# S7CAS-PLEIADES-CARTE-MERE_P07_LOW_POWER.net
KiCad netlist of a schematic drawn in Altium Designer
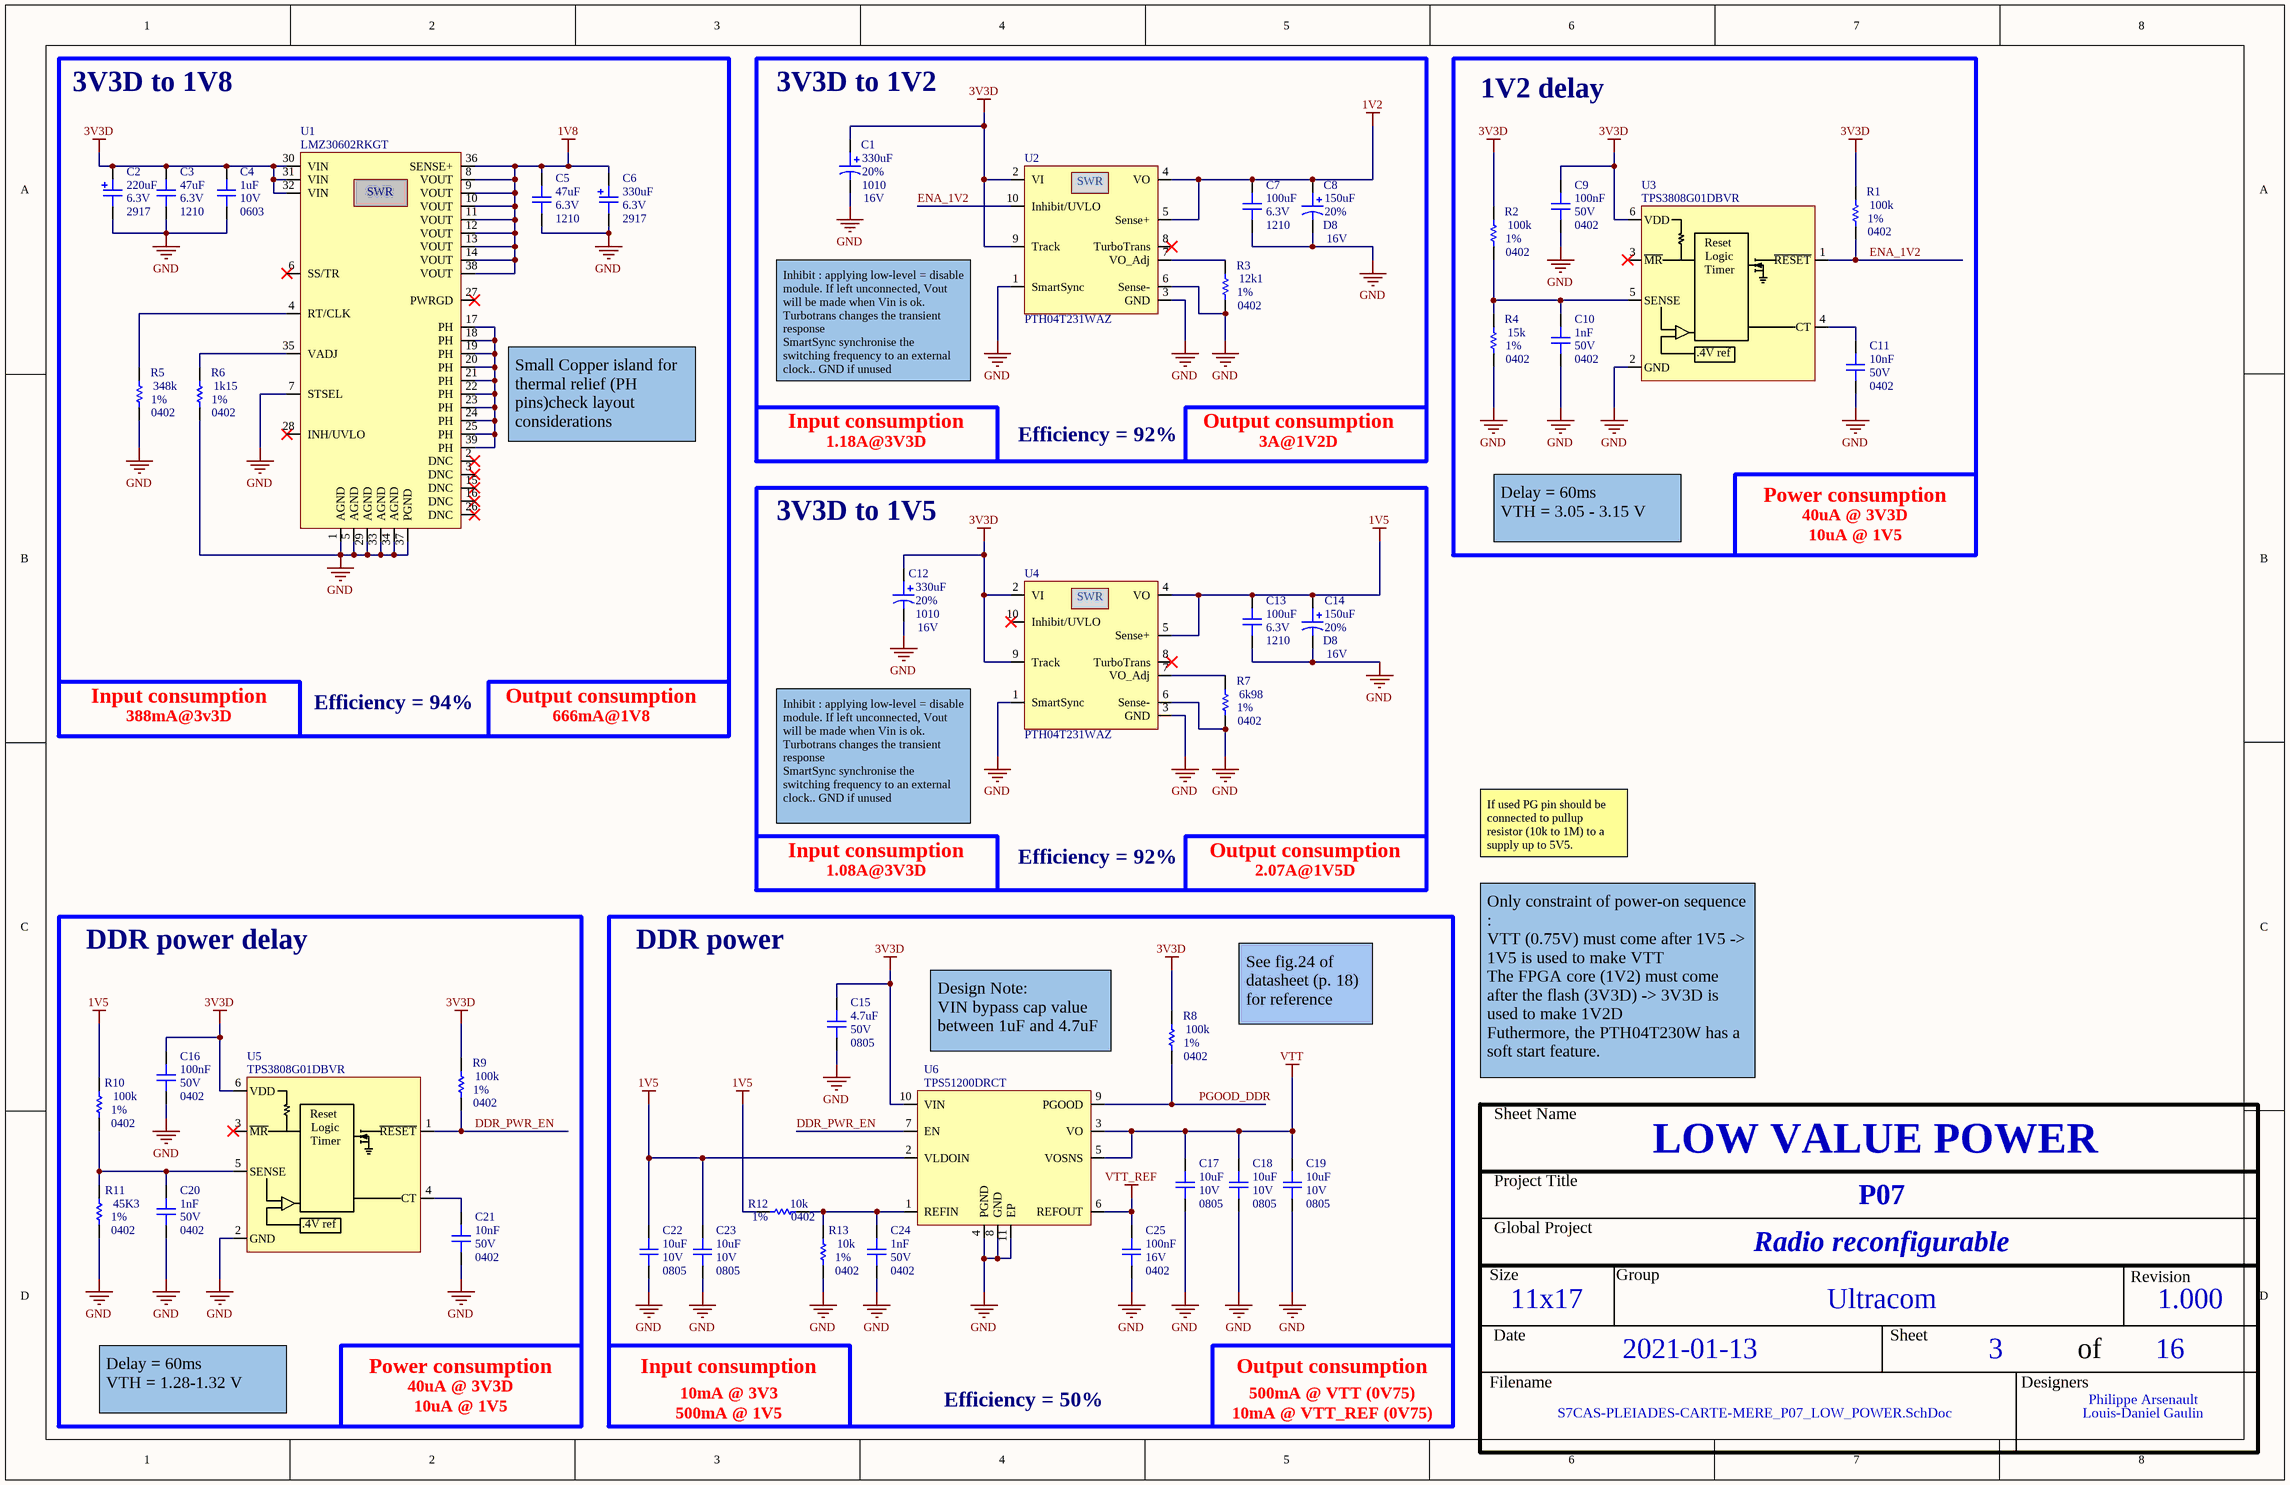
[diagram p0: S7CAS-PLEIADES-CARTE-MERE_P07_LOW_POWER.SchDoc]

(export (version "E")
  (design (tool "Eeschema 10.0.6"))
  (components
    (comp (ref "C1")
      (value "330uF")
      (footprint "CAP_ALU_1010_vishay")
      (description "CAP - ALU 330uF 20% 16V - 1010")
      (fields
        (field (name "MFG") "Vishay Dale")
        (field (name "MFG PART NUMBER") "MAL214699501E3")
        (field (name "VOLTAGE") "16V")
        (field (name "PACKAGE") "1010")
        (field (name "PRECISION") "20%")
        (field (name "CREATEDBY") "Jonathan Bouchard")
      )
      (libsource (lib "S7CAS_LIB2021") (part "CAP_ALU_MAL214699501E3"))
    )
    (comp (ref "C2")
      (value "220uF")
      (footprint "CAP_TAN_2917(D)")
      (description "CAP - TANTALUM - 2917")
      (fields
        (field (name "VOLTAGE") "6.3V")
        (field (name "PACKAGE") "2917")
        (field (name "Comment") "CAP - TANTALUM - CASE D")
        (field (name "CREATEDBY") "Jonathan Bouchard")
      )
      (libsource (lib "S7CAS_LIB2021") (part "CAP_TANT_2917(D)"))
    )
    (comp (ref "C3")
      (value "47uF")
      (footprint "CAP_1210")
      (description "CAP - 1210")
      (fields
        (field (name "VOLTAGE") "6.3V")
        (field (name "PACKAGE") "1210")
        (field (name "CREATEDBY") "Jonathan Bouchard")
      )
      (libsource (lib "S7CAS_LIB2021") (part "CAP - 1210"))
    )
    (comp (ref "C4")
      (value "1uF")
      (footprint "CAP_0603")
      (description "CAP - 0603")
      (fields
        (field (name "VOLTAGE") "10V")
        (field (name "PACKAGE") "0603")
        (field (name "CREATEDBY") "Jonathan Bouchard")
      )
      (libsource (lib "S7CAS_LIB2021") (part "CAP - 0603"))
    )
    (comp (ref "C5")
      (value "47uF")
      (footprint "CAP_1210")
      (description "CAP - 1210")
      (fields
        (field (name "VOLTAGE") "6.3V")
        (field (name "PACKAGE") "1210")
        (field (name "CREATEDBY") "Jonathan Bouchard")
      )
      (libsource (lib "S7CAS_LIB2021") (part "CAP - 1210"))
    )
    (comp (ref "C6")
      (value "330uF")
      (footprint "CAP_TAN_2917(D)")
      (description "CAP - TANTALUM - 2917")
      (fields
        (field (name "VOLTAGE") "6.3V")
        (field (name "PACKAGE") "2917")
        (field (name "Comment") "CAP - TANTALUM - CASE D")
        (field (name "CREATEDBY") "Jonathan Bouchard")
      )
      (libsource (lib "S7CAS_LIB2021") (part "CAP_TANT_2917(D)"))
    )
    (comp (ref "C7")
      (value "100uF")
      (footprint "CAP_1210")
      (description "CAP - 1210")
      (fields
        (field (name "VOLTAGE") "6.3V")
        (field (name "PACKAGE") "1210")
        (field (name "CREATEDBY") "Jonathan Bouchard")
      )
      (libsource (lib "S7CAS_LIB2021") (part "CAP - 1210"))
    )
    (comp (ref "C8")
      (value "150uF")
      (footprint "CAP_ALU_D8")
      (description "CAP ALUM 150UF 20% 16V SMD")
      (fields
        (field (name "VOLTAGE") "16V")
        (field (name "PACKAGE") "D8")
        (field (name "PRECISION") "20%")
        (field (name "Comment") "EEE-FKC151XAP")
        (field (name "CREATEDBY") "Philippe")
      )
      (libsource (lib "S7CAS_P07") (part "CAP_ALU_EEH-ZS1H151P"))
    )
    (comp (ref "C9")
      (value "100nF")
      (footprint "CAP_0402")
      (description "CAP - 0402")
      (fields
        (field (name "MFG") "C1005X7R1H102K050BA")
        (field (name "VOLTAGE") "50V")
        (field (name "PACKAGE") "0402")
        (field (name "CREATEDBY") "Jonathan Bouchard")
      )
      (libsource (lib "S7CAS_LIB2021") (part "CAP - 0402"))
    )
    (comp (ref "C10")
      (value "1nF")
      (footprint "CAP_0402")
      (description "CAP - 0402")
      (fields
        (field (name "MFG") "C1005X7R1H102K050BA")
        (field (name "VOLTAGE") "50V")
        (field (name "PACKAGE") "0402")
        (field (name "CREATEDBY") "Jonathan Bouchard")
      )
      (libsource (lib "S7CAS_LIB2021") (part "CAP - 0402"))
    )
    (comp (ref "C11")
      (value "10nF")
      (footprint "CAP_0402")
      (description "CAP - 0402")
      (fields
        (field (name "VOLTAGE") "50V")
        (field (name "PACKAGE") "0402")
        (field (name "CREATEDBY") "Jonathan Bouchard")
      )
      (libsource (lib "S7CAS_LIB2021") (part "CAP - 0402"))
    )
    (comp (ref "C12")
      (value "330uF")
      (footprint "CAP_ALU_1010_vishay")
      (description "CAP - ALU 330uF 20% 16V - 1010")
      (fields
        (field (name "MFG") "Vishay Dale")
        (field (name "MFG PART NUMBER") "MAL214699501E3")
        (field (name "VOLTAGE") "16V")
        (field (name "PACKAGE") "1010")
        (field (name "PRECISION") "20%")
        (field (name "CREATEDBY") "Jonathan Bouchard")
      )
      (libsource (lib "S7CAS_LIB2021") (part "CAP_ALU_MAL214699501E3"))
    )
    (comp (ref "C13")
      (value "100uF")
      (footprint "CAP_1210")
      (description "CAP - 1210")
      (fields
        (field (name "VOLTAGE") "6.3V")
        (field (name "PACKAGE") "1210")
        (field (name "CREATEDBY") "Jonathan Bouchard")
      )
      (libsource (lib "S7CAS_LIB2021") (part "CAP - 1210"))
    )
    (comp (ref "C14")
      (value "150uF")
      (footprint "CAP_ALU_D8")
      (description "CAP ALUM 150UF 20% 16V SMD")
      (fields
        (field (name "VOLTAGE") "16V")
        (field (name "PACKAGE") "D8")
        (field (name "PRECISION") "20%")
        (field (name "Comment") "EEE-FKC151XAP")
        (field (name "CREATEDBY") "Philippe")
      )
      (libsource (lib "S7CAS_P07") (part "CAP_ALU_EEH-ZS1H151P"))
    )
    (comp (ref "C15")
      (value "4.7uF")
      (footprint "CAP_0805")
      (description "CAP - 0805")
      (fields
        (field (name "VOLTAGE") "50V")
        (field (name "PACKAGE") "0805")
        (field (name "CREATEDBY") "Jonathan Bouchard")
      )
      (libsource (lib "S7CAS_LIB2021") (part "CAP - 0805"))
    )
    (comp (ref "C16")
      (value "100nF")
      (footprint "CAP_0402")
      (description "CAP - 0402")
      (fields
        (field (name "MFG") "C1005X7R1H102K050BA")
        (field (name "VOLTAGE") "50V")
        (field (name "PACKAGE") "0402")
        (field (name "CREATEDBY") "Jonathan Bouchard")
      )
      (libsource (lib "S7CAS_LIB2021") (part "CAP - 0402"))
    )
    (comp (ref "C17")
      (value "10uF")
      (footprint "CAP_0805")
      (description "CAP - 0805")
      (fields
        (field (name "MFG") "CL21B106KPQNNNE")
        (field (name "VOLTAGE") "10V")
        (field (name "PACKAGE") "0805")
        (field (name "CREATEDBY") "Jonathan Bouchard")
      )
      (libsource (lib "S7CAS_LIB2021") (part "CAP - 0805"))
    )
    (comp (ref "C18")
      (value "10uF")
      (footprint "CAP_0805")
      (description "CAP - 0805")
      (fields
        (field (name "MFG") "CL21B106KPQNNNE")
        (field (name "VOLTAGE") "10V")
        (field (name "PACKAGE") "0805")
        (field (name "CREATEDBY") "Jonathan Bouchard")
      )
      (libsource (lib "S7CAS_LIB2021") (part "CAP - 0805"))
    )
    (comp (ref "C19")
      (value "10uF")
      (footprint "CAP_0805")
      (description "CAP - 0805")
      (fields
        (field (name "MFG") "CL21B106KPQNNNE")
        (field (name "VOLTAGE") "10V")
        (field (name "PACKAGE") "0805")
        (field (name "CREATEDBY") "Jonathan Bouchard")
      )
      (libsource (lib "S7CAS_LIB2021") (part "CAP - 0805"))
    )
    (comp (ref "C20")
      (value "1nF")
      (footprint "CAP_0402")
      (description "CAP - 0402")
      (fields
        (field (name "MFG") "C1005X7R1H102K050BA")
        (field (name "VOLTAGE") "50V")
        (field (name "PACKAGE") "0402")
        (field (name "CREATEDBY") "Jonathan Bouchard")
      )
      (libsource (lib "S7CAS_LIB2021") (part "CAP - 0402"))
    )
    (comp (ref "C21")
      (value "10nF")
      (footprint "CAP_0402")
      (description "CAP - 0402")
      (fields
        (field (name "VOLTAGE") "50V")
        (field (name "PACKAGE") "0402")
        (field (name "CREATEDBY") "Jonathan Bouchard")
      )
      (libsource (lib "S7CAS_LIB2021") (part "CAP - 0402"))
    )
    (comp (ref "C22")
      (value "10uF")
      (footprint "CAP_0805")
      (description "CAP - 0805")
      (fields
        (field (name "MFG") "CL21B106KPQNNNE")
        (field (name "VOLTAGE") "10V")
        (field (name "PACKAGE") "0805")
        (field (name "CREATEDBY") "Jonathan Bouchard")
      )
      (libsource (lib "S7CAS_LIB2021") (part "CAP - 0805"))
    )
    (comp (ref "C23")
      (value "10uF")
      (footprint "CAP_0805")
      (description "CAP - 0805")
      (fields
        (field (name "MFG") "CL21B106KPQNNNE")
        (field (name "VOLTAGE") "10V")
        (field (name "PACKAGE") "0805")
        (field (name "CREATEDBY") "Jonathan Bouchard")
      )
      (libsource (lib "S7CAS_LIB2021") (part "CAP - 0805"))
    )
    (comp (ref "C24")
      (value "1nF")
      (footprint "CAP_0402")
      (description "CAP - 0402")
      (fields
        (field (name "MFG") "C1005X7R1H102K050BA")
        (field (name "VOLTAGE") "50V")
        (field (name "PACKAGE") "0402")
        (field (name "CREATEDBY") "Jonathan Bouchard")
      )
      (libsource (lib "S7CAS_LIB2021") (part "CAP - 0402"))
    )
    (comp (ref "C25")
      (value "100nF")
      (footprint "CAP_0402")
      (description "CAP - 0402")
      (fields
        (field (name "MFG PART NUMBER") "CL05B104KO5NNNC")
        (field (name "VOLTAGE") "16V")
        (field (name "PACKAGE") "0402")
        (field (name "CREATEDBY") "Jonathan Bouchard")
      )
      (libsource (lib "S7CAS_LIB2021") (part "CAP - 0402"))
    )
    (comp (ref "R1")
      (value "100k")
      (footprint "RES_0402")
      (description "RES - 0402")
      (fields
        (field (name "VOLTAGE") "50V")
        (field (name "POWER") "1/16W")
        (field (name "PACKAGE") "0402")
        (field (name "PRECISION") "1%")
        (field (name "CREATEDBY") "Jonathan Bouchard")
      )
      (libsource (lib "S7CAS_LIB2021") (part "RES - 0402"))
    )
    (comp (ref "R2")
      (value "100k")
      (footprint "RES_0402")
      (description "RES - 0402")
      (fields
        (field (name "VOLTAGE") "50V")
        (field (name "POWER") "1/16W")
        (field (name "PACKAGE") "0402")
        (field (name "PRECISION") "1%")
        (field (name "CREATEDBY") "Jonathan Bouchard")
      )
      (libsource (lib "S7CAS_LIB2021") (part "RES - 0402"))
    )
    (comp (ref "R3")
      (value "12k1")
      (footprint "RES_0402")
      (description "RES - 0402")
      (fields
        (field (name "VOLTAGE") "50V")
        (field (name "POWER") "1/16W")
        (field (name "PACKAGE") "0402")
        (field (name "PRECISION") "1%")
        (field (name "CREATEDBY") "Jonathan Bouchard")
      )
      (libsource (lib "S7CAS_LIB2021") (part "RES - 0402"))
    )
    (comp (ref "R4")
      (value "15k")
      (footprint "RES_0402")
      (description "RES - 0402")
      (fields
        (field (name "VOLTAGE") "50V")
        (field (name "POWER") "1/16W")
        (field (name "PACKAGE") "0402")
        (field (name "PRECISION") "1%")
        (field (name "CREATEDBY") "Jonathan Bouchard")
      )
      (libsource (lib "S7CAS_LIB2021") (part "RES - 0402"))
    )
    (comp (ref "R5")
      (value "348k")
      (footprint "RES_0402")
      (description "RES - 0402")
      (fields
        (field (name "VOLTAGE") "50V")
        (field (name "POWER") "1/16W")
        (field (name "PACKAGE") "0402")
        (field (name "PRECISION") "1%")
        (field (name "CREATEDBY") "Jonathan Bouchard")
      )
      (libsource (lib "S7CAS_LIB2021") (part "RES - 0402"))
    )
    (comp (ref "R6")
      (value "1k15")
      (footprint "RES_0402")
      (description "RES - 0402")
      (fields
        (field (name "VOLTAGE") "50V")
        (field (name "POWER") "1/16W")
        (field (name "PACKAGE") "0402")
        (field (name "PRECISION") "1%")
        (field (name "CREATEDBY") "Jonathan Bouchard")
      )
      (libsource (lib "S7CAS_LIB2021") (part "RES - 0402"))
    )
    (comp (ref "R7")
      (value "6k98")
      (footprint "RES_0402")
      (description "RES - 0402")
      (fields
        (field (name "VOLTAGE") "50V")
        (field (name "POWER") "1/16W")
        (field (name "PACKAGE") "0402")
        (field (name "PRECISION") "1%")
        (field (name "CREATEDBY") "Jonathan Bouchard")
      )
      (libsource (lib "S7CAS_LIB2021") (part "RES - 0402"))
    )
    (comp (ref "R8")
      (value "100k")
      (footprint "RES_0402")
      (description "RES - 0402")
      (fields
        (field (name "VOLTAGE") "50V")
        (field (name "POWER") "1/16W")
        (field (name "PACKAGE") "0402")
        (field (name "PRECISION") "1%")
        (field (name "CREATEDBY") "Jonathan Bouchard")
      )
      (libsource (lib "S7CAS_LIB2021") (part "RES - 0402"))
    )
    (comp (ref "R9")
      (value "100k")
      (footprint "RES_0402")
      (description "RES - 0402")
      (fields
        (field (name "VOLTAGE") "50V")
        (field (name "POWER") "1/16W")
        (field (name "PACKAGE") "0402")
        (field (name "PRECISION") "1%")
        (field (name "CREATEDBY") "Jonathan Bouchard")
      )
      (libsource (lib "S7CAS_LIB2021") (part "RES - 0402"))
    )
    (comp (ref "R10")
      (value "100k")
      (footprint "RES_0402")
      (description "RES - 0402")
      (fields
        (field (name "VOLTAGE") "50V")
        (field (name "POWER") "1/16W")
        (field (name "PACKAGE") "0402")
        (field (name "PRECISION") "1%")
        (field (name "CREATEDBY") "Jonathan Bouchard")
      )
      (libsource (lib "S7CAS_LIB2021") (part "RES - 0402"))
    )
    (comp (ref "R11")
      (value "45K3")
      (footprint "RES_0402")
      (description "RES - 0402")
      (fields
        (field (name "VOLTAGE") "50V")
        (field (name "POWER") "1/16W")
        (field (name "PACKAGE") "0402")
        (field (name "PRECISION") "1%")
        (field (name "CREATEDBY") "Jonathan Bouchard")
      )
      (libsource (lib "S7CAS_LIB2021") (part "RES - 0402"))
    )
    (comp (ref "R12")
      (value "10k")
      (footprint "RES_0402")
      (description "RES - 0402")
      (fields
        (field (name "VOLTAGE") "50V")
        (field (name "POWER") "1/16W")
        (field (name "PACKAGE") "0402")
        (field (name "PRECISION") "1%")
        (field (name "CREATEDBY") "Jonathan Bouchard")
      )
      (libsource (lib "S7CAS_LIB2021") (part "RES - 0402"))
    )
    (comp (ref "R13")
      (value "10k")
      (footprint "RES_0402")
      (description "RES - 0402")
      (fields
        (field (name "VOLTAGE") "50V")
        (field (name "POWER") "1/16W")
        (field (name "PACKAGE") "0402")
        (field (name "PRECISION") "1%")
        (field (name "CREATEDBY") "Jonathan Bouchard")
      )
      (libsource (lib "S7CAS_LIB2021") (part "RES - 0402"))
    )
    (comp (ref "U1")
      (value "LMZ30602RKGT")
      (footprint "REG_SWI_LMZ30606RKGT")
      (description "REG - DC DC Converter  \r\nNon-Isolated  Output 0.8 ~ 3.6V 2A 2.95V - 6V Input")
      (fields (field (name "CREATEDBY/DATE") "Philippe Arsenault/2021-02-01"))
      (libsource (lib "S7CAS_P07") (part "REG_SWR_LMZ30602RKGT"))
    )
    (comp (ref "U2")
      (value "PTH04T231WAZ")
      (footprint "REG_SWR_PTH04T231WAZ")
      (description "REG - MODULE PIP 6A 2.2V/5.5V - 10SMD")
      (fields
        (field (name "CREATEDBY/DATE") "Olivier Bernard / 6/5/2018")
        (field (name "VERIFIEDBY") "Caroline Paulin / 10 juillet 2018")
      )
      (libsource (lib "S7CAS_LIB2021") (part "REG_SWR_PTH04T231WAZ"))
    )
    (comp (ref "U3")
      (value "TPS3808G01DBVR")
      (footprint "POW_TPS3808G01DBVR")
      (description "POW - Programmable-Delay  Voltage Supervisory adj - SOT-23-6")
      (fields
        (field (name "CREATEDBY/DATE") "Joel Lemay 2018-11-13")
        (field (name "VERIFIEDBY") "Caroline Paulin - 22/11/2018")
      )
      (libsource (lib "S7CAS_LIB2021") (part "POW_TPS3808G01DBVR"))
    )
    (comp (ref "U4")
      (value "PTH04T231WAZ")
      (footprint "REG_SWR_PTH04T231WAZ")
      (description "REG - MODULE PIP 6A 2.2V/5.5V - 10SMD")
      (fields
        (field (name "CREATEDBY/DATE") "Olivier Bernard / 6/5/2018")
        (field (name "VERIFIEDBY") "Caroline Paulin / 10 juillet 2018")
      )
      (libsource (lib "S7CAS_LIB2021") (part "REG_SWR_PTH04T231WAZ"))
    )
    (comp (ref "U5")
      (value "TPS3808G01DBVR")
      (footprint "POW_TPS3808G01DBVR")
      (description "POW - Programmable-Delay  Voltage Supervisory adj - SOT-23-6")
      (fields
        (field (name "CREATEDBY/DATE") "Joel Lemay 2018-11-13")
        (field (name "VERIFIEDBY") "Caroline Paulin - 22/11/2018")
      )
      (libsource (lib "S7CAS_LIB2021") (part "POW_TPS3808G01DBVR"))
    )
    (comp (ref "U6")
      (value "TPS51200DRCT")
      (footprint "REG_PMIC_TPS51200DRCT")
      (description "REG - DDR TERMINATION/REF REG - 10-VFDFN")
      (fields
        (field (name "CREATEDBY/DATE") "Joel Lemay 2019-03-19")
        (field (name "VERIFIEDBY") "Nicolas V. (2019-05-31)")
      )
      (libsource (lib "S7CAS_LIB2021") (part "REG_PMIC_TPS51200DRCT"))
    )
  )
  (nets
    (net (code "1") (name "/DDR_PWR_EN") (class "Default")
      (node (ref "R9") (pin "1") (pinfunction "1_1") (pintype "passive"))
      (node (ref "U5") (pin "1") (pinfunction "~{RESET}_1") (pintype "passive"))
      (node (ref "U6") (pin "7") (pinfunction "EN_7") (pintype "passive"))
    )
    (net (code "2") (name "/ENA_1V2") (class "Default")
      (node (ref "R1") (pin "1") (pinfunction "1_1") (pintype "passive"))
      (node (ref "U2") (pin "10") (pinfunction "Inhibit/UVLO_10") (pintype "passive"))
      (node (ref "U3") (pin "1") (pinfunction "~{RESET}_1") (pintype "passive"))
    )
    (net (code "3") (name "/PGOOD_DDR") (class "Default")
      (node (ref "R8") (pin "1") (pinfunction "1_1") (pintype "passive"))
      (node (ref "U6") (pin "9") (pinfunction "PGOOD_9") (pintype "passive"))
    )
    (net (code "4") (name "1V2") (class "Default")
      (node (ref "C7") (pin "2") (pinfunction "2_2") (pintype "passive"))
      (node (ref "C8") (pin "1") (pinfunction "1_1") (pintype "passive"))
      (node (ref "U2") (pin "4") (pinfunction "VO_4") (pintype "passive"))
      (node (ref "U2") (pin "5") (pinfunction "Sense+_5") (pintype "passive"))
    )
    (net (code "5") (name "1V5") (class "Default")
      (node (ref "C13") (pin "2") (pinfunction "2_2") (pintype "passive"))
      (node (ref "C14") (pin "1") (pinfunction "1_1") (pintype "passive"))
      (node (ref "C22") (pin "2") (pinfunction "2_2") (pintype "passive"))
      (node (ref "C23") (pin "2") (pinfunction "2_2") (pintype "passive"))
      (node (ref "R10") (pin "2") (pinfunction "2_2") (pintype "passive"))
      (node (ref "R12") (pin "2") (pinfunction "2_2") (pintype "passive"))
      (node (ref "U4") (pin "4") (pinfunction "VO_4") (pintype "passive"))
      (node (ref "U4") (pin "5") (pinfunction "Sense+_5") (pintype "passive"))
      (node (ref "U6") (pin "2") (pinfunction "VLDOIN_2") (pintype "passive"))
    )
    (net (code "6") (name "1V8") (class "Default")
      (node (ref "C5") (pin "2") (pinfunction "2_2") (pintype "passive"))
      (node (ref "C6") (pin "1") (pinfunction "1_1") (pintype "passive"))
      (node (ref "U1") (pin "10") (pinfunction "VOUT_10") (pintype "passive"))
      (node (ref "U1") (pin "11") (pinfunction "VOUT_11") (pintype "passive"))
      (node (ref "U1") (pin "12") (pinfunction "VOUT_12") (pintype "passive"))
      (node (ref "U1") (pin "13") (pinfunction "VOUT_13") (pintype "passive"))
      (node (ref "U1") (pin "14") (pinfunction "VOUT_14") (pintype "passive"))
      (node (ref "U1") (pin "36") (pinfunction "SENSE+_36") (pintype "passive"))
      (node (ref "U1") (pin "38") (pinfunction "VOUT_38") (pintype "passive"))
      (node (ref "U1") (pin "8") (pinfunction "VOUT_8") (pintype "passive"))
      (node (ref "U1") (pin "9") (pinfunction "VOUT_9") (pintype "passive"))
    )
    (net (code "7") (name "3V3D") (class "Default")
      (node (ref "C1") (pin "1") (pinfunction "1_1") (pintype "passive"))
      (node (ref "C12") (pin "1") (pinfunction "1_1") (pintype "passive"))
      (node (ref "C15") (pin "2") (pinfunction "2_2") (pintype "passive"))
      (node (ref "C16") (pin "2") (pinfunction "2_2") (pintype "passive"))
      (node (ref "C2") (pin "1") (pinfunction "1_1") (pintype "passive"))
      (node (ref "C3") (pin "2") (pinfunction "2_2") (pintype "passive"))
      (node (ref "C4") (pin "2") (pinfunction "2_2") (pintype "passive"))
      (node (ref "C9") (pin "2") (pinfunction "2_2") (pintype "passive"))
      (node (ref "R1") (pin "2") (pinfunction "2_2") (pintype "passive"))
      (node (ref "R2") (pin "2") (pinfunction "2_2") (pintype "passive"))
      (node (ref "R8") (pin "2") (pinfunction "2_2") (pintype "passive"))
      (node (ref "R9") (pin "2") (pinfunction "2_2") (pintype "passive"))
      (node (ref "U1") (pin "30") (pinfunction "VIN_30") (pintype "passive"))
      (node (ref "U1") (pin "31") (pinfunction "VIN_31") (pintype "passive"))
      (node (ref "U1") (pin "32") (pinfunction "VIN_32") (pintype "passive"))
      (node (ref "U2") (pin "2") (pinfunction "VI_2") (pintype "passive"))
      (node (ref "U2") (pin "9") (pinfunction "Track_9") (pintype "passive"))
      (node (ref "U3") (pin "6") (pinfunction "VDD_6") (pintype "passive"))
      (node (ref "U4") (pin "2") (pinfunction "VI_2") (pintype "passive"))
      (node (ref "U4") (pin "9") (pinfunction "Track_9") (pintype "passive"))
      (node (ref "U5") (pin "6") (pinfunction "VDD_6") (pintype "passive"))
      (node (ref "U6") (pin "10") (pinfunction "VIN_10") (pintype "passive"))
    )
    (net (code "8") (name "GND") (class "Default")
      (node (ref "C1") (pin "2") (pinfunction "2_2") (pintype "passive"))
      (node (ref "C10") (pin "1") (pinfunction "1_1") (pintype "passive"))
      (node (ref "C11") (pin "1") (pinfunction "1_1") (pintype "passive"))
      (node (ref "C12") (pin "2") (pinfunction "2_2") (pintype "passive"))
      (node (ref "C13") (pin "1") (pinfunction "1_1") (pintype "passive"))
      (node (ref "C14") (pin "2") (pinfunction "2_2") (pintype "passive"))
      (node (ref "C15") (pin "1") (pinfunction "1_1") (pintype "passive"))
      (node (ref "C16") (pin "1") (pinfunction "1_1") (pintype "passive"))
      (node (ref "C17") (pin "1") (pinfunction "1_1") (pintype "passive"))
      (node (ref "C18") (pin "1") (pinfunction "1_1") (pintype "passive"))
      (node (ref "C19") (pin "1") (pinfunction "1_1") (pintype "passive"))
      (node (ref "C2") (pin "2") (pinfunction "2_2") (pintype "passive"))
      (node (ref "C20") (pin "1") (pinfunction "1_1") (pintype "passive"))
      (node (ref "C21") (pin "1") (pinfunction "1_1") (pintype "passive"))
      (node (ref "C22") (pin "1") (pinfunction "1_1") (pintype "passive"))
      (node (ref "C23") (pin "1") (pinfunction "1_1") (pintype "passive"))
      (node (ref "C24") (pin "1") (pinfunction "1_1") (pintype "passive"))
      (node (ref "C25") (pin "1") (pinfunction "1_1") (pintype "passive"))
      (node (ref "C3") (pin "1") (pinfunction "1_1") (pintype "passive"))
      (node (ref "C4") (pin "1") (pinfunction "1_1") (pintype "passive"))
      (node (ref "C5") (pin "1") (pinfunction "1_1") (pintype "passive"))
      (node (ref "C6") (pin "2") (pinfunction "2_2") (pintype "passive"))
      (node (ref "C7") (pin "1") (pinfunction "1_1") (pintype "passive"))
      (node (ref "C8") (pin "2") (pinfunction "2_2") (pintype "passive"))
      (node (ref "C9") (pin "1") (pinfunction "1_1") (pintype "passive"))
      (node (ref "R11") (pin "1") (pinfunction "1_1") (pintype "passive"))
      (node (ref "R13") (pin "1") (pinfunction "1_1") (pintype "passive"))
      (node (ref "R3") (pin "1") (pinfunction "1_1") (pintype "passive"))
      (node (ref "R4") (pin "1") (pinfunction "1_1") (pintype "passive"))
      (node (ref "R5") (pin "1") (pinfunction "1_1") (pintype "passive"))
      (node (ref "R6") (pin "1") (pinfunction "1_1") (pintype "passive"))
      (node (ref "R7") (pin "1") (pinfunction "1_1") (pintype "passive"))
      (node (ref "U1") (pin "1") (pinfunction "AGND_1") (pintype "passive"))
      (node (ref "U1") (pin "29") (pinfunction "AGND_29") (pintype "passive"))
      (node (ref "U1") (pin "33") (pinfunction "AGND_33") (pintype "passive"))
      (node (ref "U1") (pin "34") (pinfunction "AGND_34") (pintype "passive"))
      (node (ref "U1") (pin "37") (pinfunction "PGND_37") (pintype "passive"))
      (node (ref "U1") (pin "5") (pinfunction "AGND_5") (pintype "passive"))
      (node (ref "U1") (pin "7") (pinfunction "STSEL_7") (pintype "passive"))
      (node (ref "U2") (pin "1") (pinfunction "SmartSync_1") (pintype "passive"))
      (node (ref "U2") (pin "3") (pinfunction "GND_3") (pintype "passive"))
      (node (ref "U2") (pin "6") (pinfunction "Sense-_6") (pintype "passive"))
      (node (ref "U3") (pin "2") (pinfunction "GND_2") (pintype "passive"))
      (node (ref "U4") (pin "1") (pinfunction "SmartSync_1") (pintype "passive"))
      (node (ref "U4") (pin "3") (pinfunction "GND_3") (pintype "passive"))
      (node (ref "U4") (pin "6") (pinfunction "Sense-_6") (pintype "passive"))
      (node (ref "U5") (pin "2") (pinfunction "GND_2") (pintype "passive"))
      (node (ref "U6") (pin "11") (pinfunction "EP_11") (pintype "passive"))
      (node (ref "U6") (pin "4") (pinfunction "PGND_4") (pintype "passive"))
      (node (ref "U6") (pin "8") (pinfunction "GND_8") (pintype "passive"))
    )
    (net (code "9") (name "Net-(U1-PH-Pad17)") (class "Default")
      (node (ref "U1") (pin "17") (pinfunction "PH_17") (pintype "passive"))
      (node (ref "U1") (pin "18") (pinfunction "PH_18") (pintype "passive"))
      (node (ref "U1") (pin "19") (pinfunction "PH_19") (pintype "passive"))
      (node (ref "U1") (pin "20") (pinfunction "PH_20") (pintype "passive"))
      (node (ref "U1") (pin "21") (pinfunction "PH_21") (pintype "passive"))
      (node (ref "U1") (pin "22") (pinfunction "PH_22") (pintype "passive"))
      (node (ref "U1") (pin "23") (pinfunction "PH_23") (pintype "passive"))
      (node (ref "U1") (pin "24") (pinfunction "PH_24") (pintype "passive"))
      (node (ref "U1") (pin "25") (pinfunction "PH_25") (pintype "passive"))
      (node (ref "U1") (pin "39") (pinfunction "PH_39") (pintype "passive"))
    )
    (net (code "10") (name "Net-(U1-RT{slash}CLK)") (class "Default")
      (node (ref "R5") (pin "2") (pinfunction "2_2") (pintype "passive"))
      (node (ref "U1") (pin "4") (pinfunction "RT/CLK_4") (pintype "passive"))
    )
    (net (code "11") (name "Net-(U1-VADJ)") (class "Default")
      (node (ref "R6") (pin "2") (pinfunction "2_2") (pintype "passive"))
      (node (ref "U1") (pin "35") (pinfunction "VADJ_35") (pintype "passive"))
    )
    (net (code "12") (name "Net-(U2-VO_Adj)") (class "Default")
      (node (ref "R3") (pin "2") (pinfunction "2_2") (pintype "passive"))
      (node (ref "U2") (pin "7") (pinfunction "VO_Adj_7") (pintype "passive"))
    )
    (net (code "13") (name "Net-(U3-CT)") (class "Default")
      (node (ref "C11") (pin "2") (pinfunction "2_2") (pintype "passive"))
      (node (ref "U3") (pin "4") (pinfunction "CT_4") (pintype "passive"))
    )
    (net (code "14") (name "Net-(U3-SENSE)") (class "Default")
      (node (ref "C10") (pin "2") (pinfunction "2_2") (pintype "passive"))
      (node (ref "R2") (pin "1") (pinfunction "1_1") (pintype "passive"))
      (node (ref "R4") (pin "2") (pinfunction "2_2") (pintype "passive"))
      (node (ref "U3") (pin "5") (pinfunction "SENSE_5") (pintype "passive"))
    )
    (net (code "15") (name "Net-(U4-VO_Adj)") (class "Default")
      (node (ref "R7") (pin "2") (pinfunction "2_2") (pintype "passive"))
      (node (ref "U4") (pin "7") (pinfunction "VO_Adj_7") (pintype "passive"))
    )
    (net (code "16") (name "Net-(U5-CT)") (class "Default")
      (node (ref "C21") (pin "2") (pinfunction "2_2") (pintype "passive"))
      (node (ref "U5") (pin "4") (pinfunction "CT_4") (pintype "passive"))
    )
    (net (code "17") (name "Net-(U5-SENSE)") (class "Default")
      (node (ref "C20") (pin "2") (pinfunction "2_2") (pintype "passive"))
      (node (ref "R10") (pin "1") (pinfunction "1_1") (pintype "passive"))
      (node (ref "R11") (pin "2") (pinfunction "2_2") (pintype "passive"))
      (node (ref "U5") (pin "5") (pinfunction "SENSE_5") (pintype "passive"))
    )
    (net (code "18") (name "Net-(U6-REFIN)") (class "Default")
      (node (ref "C24") (pin "2") (pinfunction "2_2") (pintype "passive"))
      (node (ref "R12") (pin "1") (pinfunction "1_1") (pintype "passive"))
      (node (ref "R13") (pin "2") (pinfunction "2_2") (pintype "passive"))
      (node (ref "U6") (pin "1") (pinfunction "REFIN_1") (pintype "passive"))
    )
    (net (code "19") (name "VTT") (class "Default")
      (node (ref "C17") (pin "2") (pinfunction "2_2") (pintype "passive"))
      (node (ref "C18") (pin "2") (pinfunction "2_2") (pintype "passive"))
      (node (ref "C19") (pin "2") (pinfunction "2_2") (pintype "passive"))
      (node (ref "U6") (pin "3") (pinfunction "VO_3") (pintype "passive"))
      (node (ref "U6") (pin "5") (pinfunction "VOSNS_5") (pintype "passive"))
    )
    (net (code "20") (name "VTT_REF") (class "Default")
      (node (ref "C25") (pin "2") (pinfunction "2_2") (pintype "passive"))
      (node (ref "U6") (pin "6") (pinfunction "REFOUT_6") (pintype "passive"))
    )
    (net (code "21") (name "unconnected-(U1-DNC-Pad2)") (class "Default")
      (node (ref "U1") (pin "2") (pinfunction "DNC_2") (pintype "passive+no_connect"))
    )
    (net (code "22") (name "unconnected-(U1-DNC-Pad3)") (class "Default")
      (node (ref "U1") (pin "3") (pinfunction "DNC_3") (pintype "passive+no_connect"))
    )
    (net (code "23") (name "unconnected-(U1-DNC-Pad15)") (class "Default")
      (node (ref "U1") (pin "15") (pinfunction "DNC_15") (pintype "passive+no_connect"))
    )
    (net (code "24") (name "unconnected-(U1-DNC-Pad16)") (class "Default")
      (node (ref "U1") (pin "16") (pinfunction "DNC_16") (pintype "passive+no_connect"))
    )
    (net (code "25") (name "unconnected-(U1-DNC-Pad26)") (class "Default")
      (node (ref "U1") (pin "26") (pinfunction "DNC_26") (pintype "passive+no_connect"))
    )
    (net (code "26") (name "unconnected-(U1-INH{slash}UVLO-Pad28)") (class "Default")
      (node (ref "U1") (pin "28") (pinfunction "INH/UVLO_28") (pintype "passive+no_connect"))
    )
    (net (code "27") (name "unconnected-(U1-PWRGD-Pad27)") (class "Default")
      (node (ref "U1") (pin "27") (pinfunction "PWRGD_27") (pintype "passive+no_connect"))
    )
    (net (code "28") (name "unconnected-(U1-SS{slash}TR-Pad6)") (class "Default")
      (node (ref "U1") (pin "6") (pinfunction "SS/TR_6") (pintype "passive+no_connect"))
    )
    (net (code "29") (name "unconnected-(U2-TurboTrans-Pad8)") (class "Default")
      (node (ref "U2") (pin "8") (pinfunction "TurboTrans_8") (pintype "passive+no_connect"))
    )
    (net (code "30") (name "unconnected-(U3-~{MR}-Pad3)") (class "Default")
      (node (ref "U3") (pin "3") (pinfunction "~{MR}_3") (pintype "passive+no_connect"))
    )
    (net (code "31") (name "unconnected-(U4-Inhibit{slash}UVLO-Pad10)") (class "Default")
      (node (ref "U4") (pin "10") (pinfunction "Inhibit/UVLO_10") (pintype "passive+no_connect"))
    )
    (net (code "32") (name "unconnected-(U4-TurboTrans-Pad8)") (class "Default")
      (node (ref "U4") (pin "8") (pinfunction "TurboTrans_8") (pintype "passive+no_connect"))
    )
    (net (code "33") (name "unconnected-(U5-~{MR}-Pad3)") (class "Default")
      (node (ref "U5") (pin "3") (pinfunction "~{MR}_3") (pintype "passive+no_connect"))
    )
  )
)
